# DriverAxis.net
KiCad netlist of a schematic drawn in Altium Designer
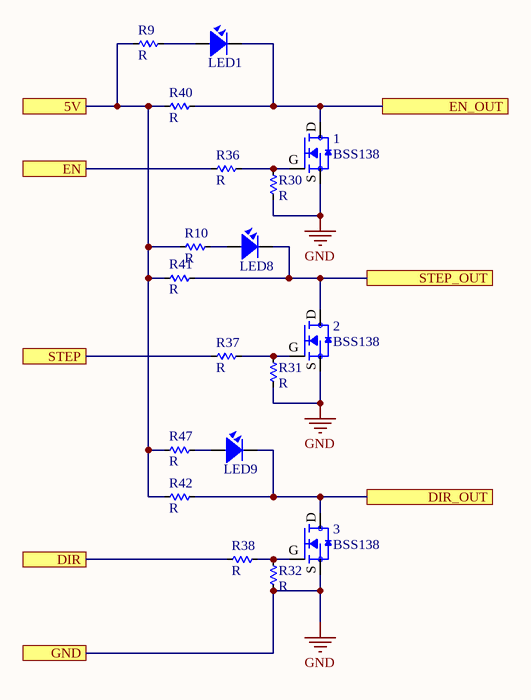
[diagram p0: DriverAxis.SchDoc]

(export (version "E")
  (design (tool "Eeschema 10.0.6"))
  (components
    (comp (ref "1")
      (value "BSS138")
      (footprint "SOT23-bss138")
      (description "N-Channel 50V 220mA _Ta_ 360mW _Ta_ Surface Mount Die")
      (fields (field (name "MF") "MICROSS/On Semiconductor"))
      (libsource (lib "nhan") (part "BSS138"))
    )
    (comp (ref "2")
      (value "BSS138")
      (footprint "SOT23-bss138")
      (description "N-Channel 50V 220mA _Ta_ 360mW _Ta_ Surface Mount Die")
      (fields (field (name "MF") "MICROSS/On Semiconductor"))
      (libsource (lib "nhan") (part "BSS138"))
    )
    (comp (ref "3")
      (value "BSS138")
      (footprint "SOT23-bss138")
      (description "N-Channel 50V 220mA _Ta_ 360mW _Ta_ Surface Mount Die")
      (fields (field (name "MF") "MICROSS/On Semiconductor"))
      (libsource (lib "nhan") (part "BSS138"))
    )
    (comp (ref "LED1")
      (value "LED")
      (footprint "LED-0805-Blue")
      (libsource (lib "BanLinhKien") (part "LED SMD"))
    )
    (comp (ref "LED8")
      (value "LED")
      (footprint "LED-0805-Blue")
      (libsource (lib "BanLinhKien") (part "LED SMD"))
    )
    (comp (ref "LED9")
      (value "LED")
      (footprint "LED-0805-Blue")
      (libsource (lib "BanLinhKien") (part "LED SMD"))
    )
    (comp (ref "R9") (value "R") (footprint "RES-SMD-0603_BIG") (libsource (lib "nhan") (part "R")))
    (comp (ref "R10") (value "R") (footprint "RES-SMD-0603_BIG") (libsource (lib "nhan") (part "R")))
    (comp (ref "R30") (value "R") (footprint "RES-SMD-0603_BIG") (libsource (lib "nhan") (part "R")))
    (comp (ref "R31") (value "R") (footprint "RES-SMD-0603_BIG") (libsource (lib "nhan") (part "R")))
    (comp (ref "R32") (value "R") (footprint "RES-SMD-0603_BIG") (libsource (lib "nhan") (part "R")))
    (comp (ref "R36") (value "R") (footprint "RES-SMD-0603_BIG") (libsource (lib "nhan") (part "R")))
    (comp (ref "R37") (value "R") (footprint "RES-SMD-0603_BIG") (libsource (lib "nhan") (part "R")))
    (comp (ref "R38") (value "R") (footprint "RES-SMD-0603_BIG") (libsource (lib "nhan") (part "R")))
    (comp (ref "R40") (value "R") (footprint "RES-SMD-0603_BIG") (libsource (lib "nhan") (part "R")))
    (comp (ref "R41") (value "R") (footprint "RES-SMD-0603_BIG") (libsource (lib "nhan") (part "R")))
    (comp (ref "R42") (value "R") (footprint "RES-SMD-0603_BIG") (libsource (lib "nhan") (part "R")))
    (comp (ref "R47") (value "R") (footprint "RES-SMD-0603_BIG") (libsource (lib "nhan") (part "R")))
  )
  (nets
    (net (code "1") (name "/5V") (class "Default")
      (node (ref "R10") (pin "1") (pinfunction "1_1") (pintype "passive"))
      (node (ref "R40") (pin "1") (pinfunction "1_1") (pintype "passive"))
      (node (ref "R41") (pin "1") (pinfunction "1_1") (pintype "passive"))
      (node (ref "R42") (pin "1") (pinfunction "1_1") (pintype "passive"))
      (node (ref "R47") (pin "1") (pinfunction "1_1") (pintype "passive"))
      (node (ref "R9") (pin "1") (pinfunction "1_1") (pintype "passive"))
    )
    (net (code "2") (name "/DIR") (class "Default")
      (node (ref "R38") (pin "1") (pinfunction "1_1") (pintype "passive"))
    )
    (net (code "3") (name "/DIR_OUT") (class "Default")
      (node (ref "3") (pin "D") (pinfunction "D_D") (pintype "passive"))
      (node (ref "LED9") (pin "2") (pinfunction "2_2") (pintype "passive"))
      (node (ref "R42") (pin "2") (pinfunction "2_2") (pintype "passive"))
    )
    (net (code "4") (name "/EN") (class "Default")
      (node (ref "R36") (pin "1") (pinfunction "1_1") (pintype "passive"))
    )
    (net (code "5") (name "/EN_OUT") (class "Default")
      (node (ref "1") (pin "D") (pinfunction "D_D") (pintype "passive"))
      (node (ref "LED1") (pin "2") (pinfunction "2_2") (pintype "passive"))
      (node (ref "R40") (pin "2") (pinfunction "2_2") (pintype "passive"))
    )
    (net (code "6") (name "/STEP") (class "Default")
      (node (ref "R37") (pin "1") (pinfunction "1_1") (pintype "passive"))
    )
    (net (code "7") (name "/STEP_OUT") (class "Default")
      (node (ref "2") (pin "D") (pinfunction "D_D") (pintype "passive"))
      (node (ref "LED8") (pin "2") (pinfunction "2_2") (pintype "passive"))
      (node (ref "R41") (pin "2") (pinfunction "2_2") (pintype "passive"))
    )
    (net (code "8") (name "GND") (class "Default")
      (node (ref "1") (pin "S") (pinfunction "S_S") (pintype "passive"))
      (node (ref "2") (pin "S") (pinfunction "S_S") (pintype "passive"))
      (node (ref "3") (pin "S") (pinfunction "S_S") (pintype "passive"))
      (node (ref "R30") (pin "2") (pinfunction "2_2") (pintype "passive"))
      (node (ref "R31") (pin "2") (pinfunction "2_2") (pintype "passive"))
      (node (ref "R32") (pin "2") (pinfunction "2_2") (pintype "passive"))
    )
    (net (code "9") (name "Net-(1-PadG)") (class "Default")
      (node (ref "1") (pin "G") (pinfunction "G_G") (pintype "passive"))
      (node (ref "R30") (pin "1") (pinfunction "1_1") (pintype "passive"))
      (node (ref "R36") (pin "2") (pinfunction "2_2") (pintype "passive"))
    )
    (net (code "10") (name "Net-(2-PadG)") (class "Default")
      (node (ref "2") (pin "G") (pinfunction "G_G") (pintype "passive"))
      (node (ref "R31") (pin "1") (pinfunction "1_1") (pintype "passive"))
      (node (ref "R37") (pin "2") (pinfunction "2_2") (pintype "passive"))
    )
    (net (code "11") (name "Net-(3-PadG)") (class "Default")
      (node (ref "3") (pin "G") (pinfunction "G_G") (pintype "passive"))
      (node (ref "R32") (pin "1") (pinfunction "1_1") (pintype "passive"))
      (node (ref "R38") (pin "2") (pinfunction "2_2") (pintype "passive"))
    )
    (net (code "12") (name "Net-(LED1-Pad1)") (class "Default")
      (node (ref "LED1") (pin "1") (pinfunction "1_1") (pintype "passive"))
      (node (ref "R9") (pin "2") (pinfunction "2_2") (pintype "passive"))
    )
    (net (code "13") (name "Net-(LED8-Pad1)") (class "Default")
      (node (ref "LED8") (pin "1") (pinfunction "1_1") (pintype "passive"))
      (node (ref "R10") (pin "2") (pinfunction "2_2") (pintype "passive"))
    )
    (net (code "14") (name "Net-(LED9-Pad1)") (class "Default")
      (node (ref "LED9") (pin "1") (pinfunction "1_1") (pintype "passive"))
      (node (ref "R47") (pin "2") (pinfunction "2_2") (pintype "passive"))
    )
  )
)
